# BSF.net
KiCad netlist of a schematic drawn in EAGLE
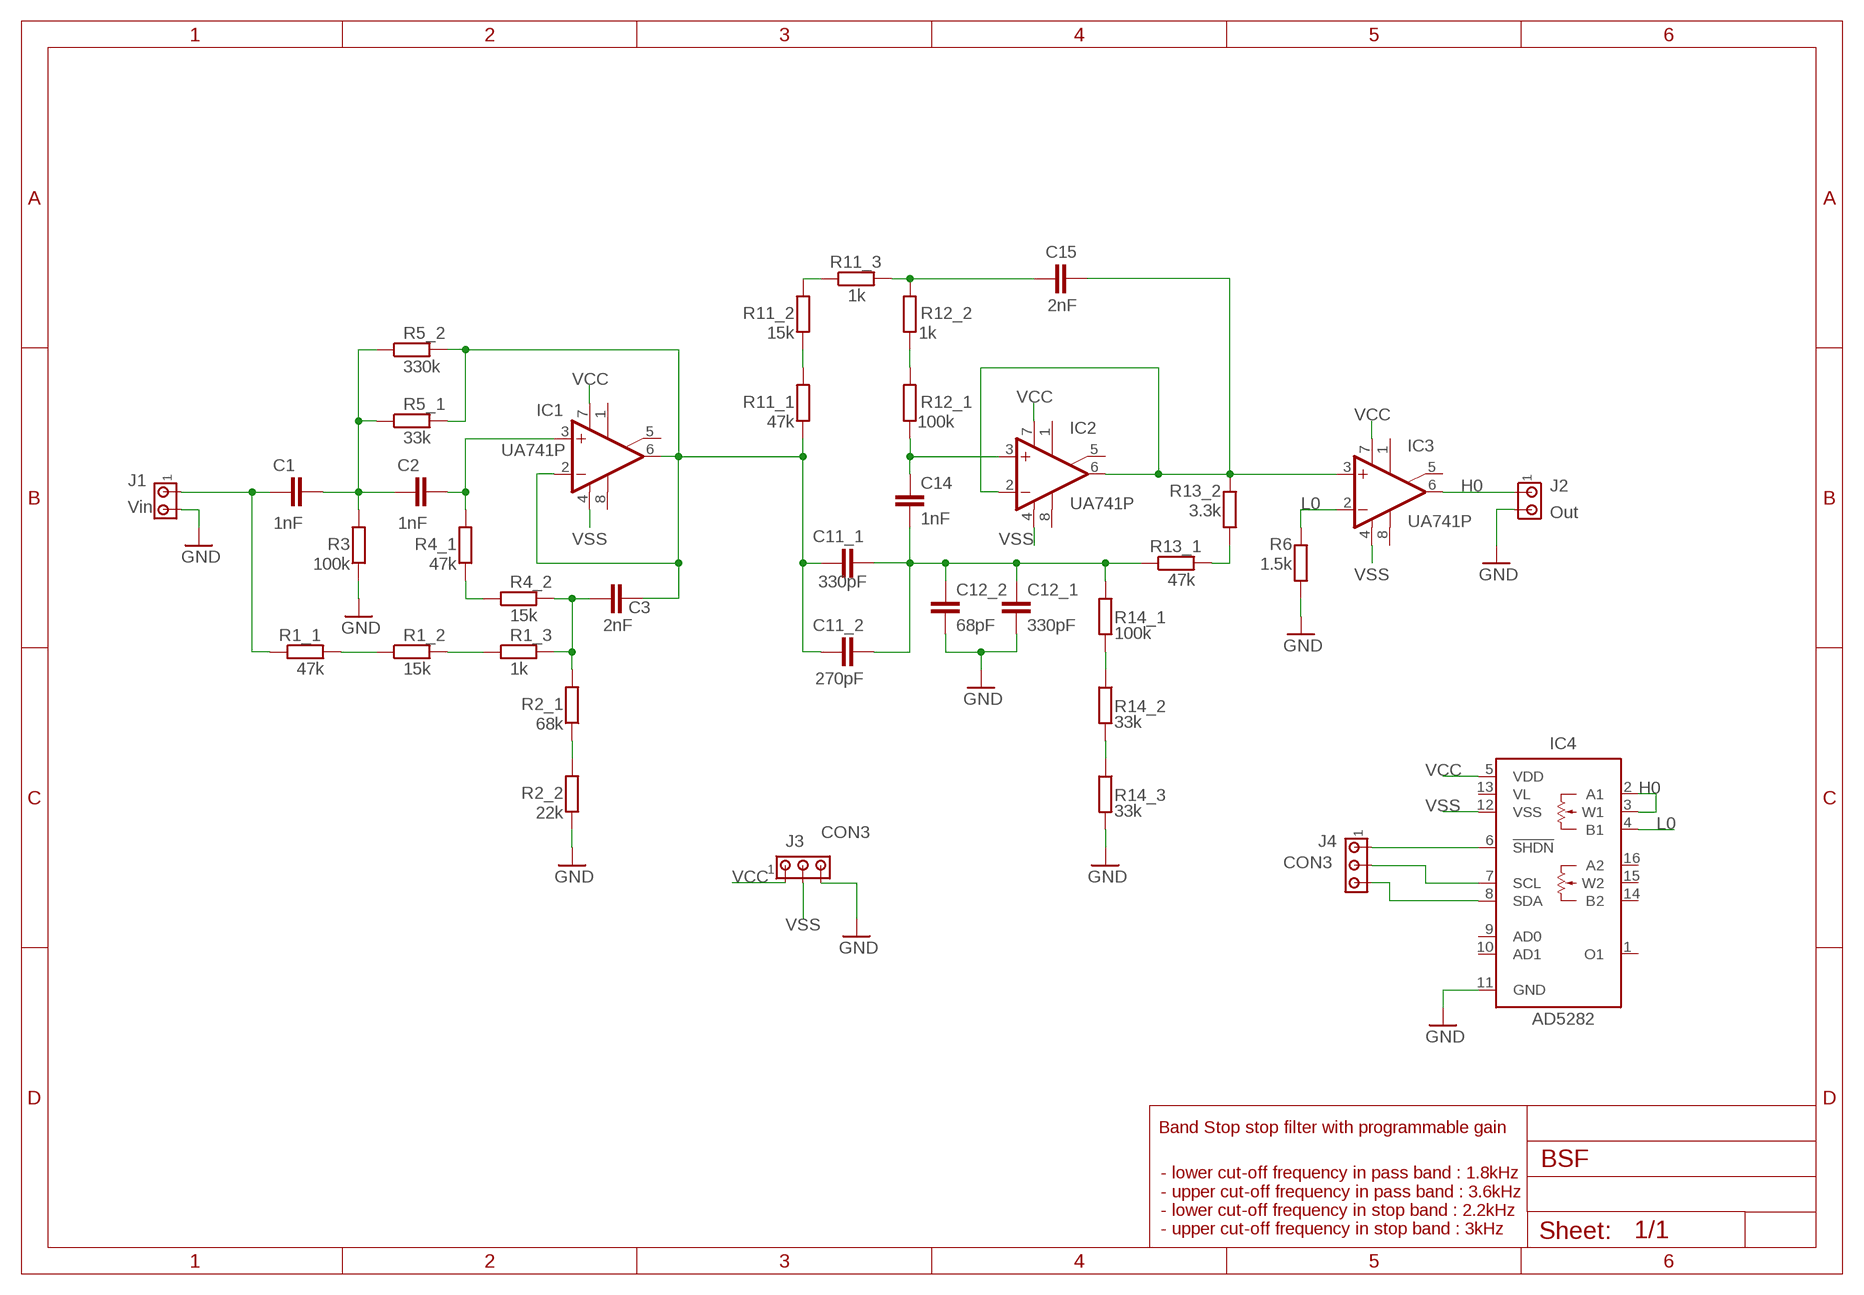
[diagram p0: schematic, sheet 1]

(export (version "E")
  (design (tool "Eeschema 10.0.6"))
  (components
    (comp (ref "C1")
      (value "1nF")
      (footprint "eagle-import:C0805")
      (libsource (lib "eagle-import") (part "C-EUC0805"))
    )
    (comp (ref "C2")
      (value "1nF")
      (footprint "eagle-import:C0805")
      (libsource (lib "eagle-import") (part "C-EUC0805"))
    )
    (comp (ref "C3")
      (value "2nF")
      (footprint "eagle-import:C0805")
      (libsource (lib "eagle-import") (part "C-EUC0805"))
    )
    (comp (ref "C11_1")
      (value "330pF")
      (footprint "eagle-import:C0805")
      (libsource (lib "eagle-import") (part "C-EUC0805"))
    )
    (comp (ref "C11_2")
      (value "270pF")
      (footprint "eagle-import:C0805")
      (libsource (lib "eagle-import") (part "C-EUC0805"))
    )
    (comp (ref "C12_1")
      (value "330pF")
      (footprint "eagle-import:C0805")
      (libsource (lib "eagle-import") (part "C-EUC0805"))
    )
    (comp (ref "C12_2")
      (value "68pF")
      (footprint "eagle-import:C0805")
      (libsource (lib "eagle-import") (part "C-EUC0805"))
    )
    (comp (ref "C14")
      (value "1nF")
      (footprint "eagle-import:C0805")
      (libsource (lib "eagle-import") (part "C-EUC0805"))
    )
    (comp (ref "C15")
      (value "2nF")
      (footprint "eagle-import:C0805")
      (libsource (lib "eagle-import") (part "C-EUC0805"))
    )
    (comp (ref "IC1")
      (value "UA741P")
      (footprint "eagle-import:DIL08")
      (libsource (lib "eagle-import") (part "741PUA"))
    )
    (comp (ref "IC2")
      (value "UA741P")
      (footprint "eagle-import:DIL08")
      (libsource (lib "eagle-import") (part "741PUA"))
    )
    (comp (ref "IC3")
      (value "UA741P")
      (footprint "eagle-import:DIL08")
      (libsource (lib "eagle-import") (part "741PUA"))
    )
    (comp (ref "IC4")
      (value "AD5282")
      (footprint "eagle-import:TSSOP16")
      (fields (field (name "MF") "ALTERA CORPORATION") (field (name "MPN") "AD5282BRUZ50"))
      (libsource (lib "eagle-import") (part "AD5282"))
    )
    (comp (ref "J1")
      (value "Vin")
      (footprint "eagle-import:1X2MTA")
      (libsource (lib "eagle-import") (part "MTA02-156"))
    )
    (comp (ref "J2")
      (value "Out")
      (footprint "eagle-import:1X2MTA")
      (libsource (lib "eagle-import") (part "MTA02-156"))
    )
    (comp (ref "J3")
      (value "CON3")
      (footprint "eagle-import:1X3MTA")
      (libsource (lib "eagle-import") (part "MTA03-156"))
    )
    (comp (ref "J4")
      (value "CON3")
      (footprint "eagle-import:1X3MTA")
      (libsource (lib "eagle-import") (part "MTA03-156"))
    )
    (comp (ref "R1_1")
      (value "47k")
      (footprint "eagle-import:R0805")
      (libsource (lib "eagle-import") (part "R-EU_R0805"))
    )
    (comp (ref "R1_2")
      (value "15k")
      (footprint "eagle-import:R0805")
      (libsource (lib "eagle-import") (part "R-EU_R0805"))
    )
    (comp (ref "R1_3")
      (value "1k")
      (footprint "eagle-import:R0805")
      (libsource (lib "eagle-import") (part "R-EU_R0805"))
    )
    (comp (ref "R2_1")
      (value "68k")
      (footprint "eagle-import:R0805")
      (libsource (lib "eagle-import") (part "R-EU_R0805"))
    )
    (comp (ref "R2_2")
      (value "22k")
      (footprint "eagle-import:R0805")
      (libsource (lib "eagle-import") (part "R-EU_R0805"))
    )
    (comp (ref "R3")
      (value "100k")
      (footprint "eagle-import:R0805")
      (libsource (lib "eagle-import") (part "R-EU_R0805"))
    )
    (comp (ref "R4_1")
      (value "47k")
      (footprint "eagle-import:R0805")
      (libsource (lib "eagle-import") (part "R-EU_R0805"))
    )
    (comp (ref "R4_2")
      (value "15k")
      (footprint "eagle-import:R0805")
      (libsource (lib "eagle-import") (part "R-EU_R0805"))
    )
    (comp (ref "R5_1")
      (value "33k")
      (footprint "eagle-import:R0805")
      (libsource (lib "eagle-import") (part "R-EU_R0805"))
    )
    (comp (ref "R5_2")
      (value "330k")
      (footprint "eagle-import:R0805")
      (libsource (lib "eagle-import") (part "R-EU_R0805"))
    )
    (comp (ref "R6")
      (value "1.5k")
      (footprint "eagle-import:R0805")
      (libsource (lib "eagle-import") (part "R-EU_R0805"))
    )
    (comp (ref "R11_1")
      (value "47k")
      (footprint "eagle-import:R0805")
      (libsource (lib "eagle-import") (part "R-EU_R0805"))
    )
    (comp (ref "R11_2")
      (value "15k")
      (footprint "eagle-import:R0805")
      (libsource (lib "eagle-import") (part "R-EU_R0805"))
    )
    (comp (ref "R11_3")
      (value "1k")
      (footprint "eagle-import:R0805")
      (libsource (lib "eagle-import") (part "R-EU_R0805"))
    )
    (comp (ref "R12_1")
      (value "100k")
      (footprint "eagle-import:R0805")
      (libsource (lib "eagle-import") (part "R-EU_R0805"))
    )
    (comp (ref "R12_2")
      (value "1k")
      (footprint "eagle-import:R0805")
      (libsource (lib "eagle-import") (part "R-EU_R0805"))
    )
    (comp (ref "R13_1")
      (value "47k")
      (footprint "eagle-import:R0805")
      (libsource (lib "eagle-import") (part "R-EU_R0805"))
    )
    (comp (ref "R13_2")
      (value "3.3k")
      (footprint "eagle-import:R0805")
      (libsource (lib "eagle-import") (part "R-EU_R0805"))
    )
    (comp (ref "R14_1")
      (value "100k")
      (footprint "eagle-import:R0805")
      (libsource (lib "eagle-import") (part "R-EU_R0805"))
    )
    (comp (ref "R14_2")
      (value "33k")
      (footprint "eagle-import:R0805")
      (libsource (lib "eagle-import") (part "R-EU_R0805"))
    )
    (comp (ref "R14_3")
      (value "33k")
      (footprint "eagle-import:R0805")
      (libsource (lib "eagle-import") (part "R-EU_R0805"))
    )
  )
  (nets
    (net (code "1") (name "/H0") (class "Default")
      (node (ref "IC3") (pin "6") (pinfunction "OUT_6") (pintype "output"))
      (node (ref "IC4") (pin "2") (pinfunction "A1_2") (pintype "passive"))
      (node (ref "IC4") (pin "3") (pinfunction "W1_3") (pintype "passive"))
      (node (ref "J2") (pin "1") (pinfunction "1_1") (pintype "passive"))
    )
    (net (code "2") (name "/L0") (class "Default")
      (node (ref "IC3") (pin "2") (pinfunction "-IN_2") (pintype "input"))
      (node (ref "IC4") (pin "4") (pinfunction "B1_4") (pintype "passive"))
      (node (ref "R6") (pin "2") (pinfunction "2_2") (pintype "passive"))
    )
    (net (code "3") (name "/VCC") (class "Default")
      (node (ref "IC1") (pin "7") (pinfunction "V+_7") (pintype "power_in"))
      (node (ref "IC2") (pin "7") (pinfunction "V+_7") (pintype "power_in"))
      (node (ref "IC3") (pin "7") (pinfunction "V+_7") (pintype "power_in"))
      (node (ref "IC4") (pin "5") (pinfunction "VDD_5") (pintype "power_in"))
      (node (ref "J3") (pin "1") (pinfunction "1_1") (pintype "passive"))
    )
    (net (code "4") (name "/VL") (class "Default")
      (node (ref "IC4") (pin "13") (pinfunction "VL_13") (pintype "power_in"))
    )
    (net (code "5") (name "/VSS") (class "Default")
      (node (ref "IC1") (pin "4") (pinfunction "V-_4") (pintype "power_in"))
      (node (ref "IC2") (pin "4") (pinfunction "V-_4") (pintype "power_in"))
      (node (ref "IC3") (pin "4") (pinfunction "V-_4") (pintype "power_in"))
      (node (ref "IC4") (pin "12") (pinfunction "VSS_12") (pintype "power_in"))
      (node (ref "J3") (pin "2") (pinfunction "2_2") (pintype "passive"))
    )
    (net (code "6") (name "GND") (class "Default")
      (node (ref "C12_1") (pin "2") (pinfunction "2_2") (pintype "passive"))
      (node (ref "C12_2") (pin "2") (pinfunction "2_2") (pintype "passive"))
      (node (ref "IC4") (pin "11") (pinfunction "GND_11") (pintype "power_in"))
      (node (ref "J1") (pin "2") (pinfunction "2_2") (pintype "passive"))
      (node (ref "J2") (pin "2") (pinfunction "2_2") (pintype "passive"))
      (node (ref "J3") (pin "3") (pinfunction "3_3") (pintype "passive"))
      (node (ref "R14_3") (pin "2") (pinfunction "2_2") (pintype "passive"))
      (node (ref "R2_2") (pin "1") (pinfunction "1_1") (pintype "passive"))
      (node (ref "R3") (pin "1") (pinfunction "1_1") (pintype "passive"))
      (node (ref "R6") (pin "1") (pinfunction "1_1") (pintype "passive"))
    )
    (net (code "7") (name "Net-(C1-Pad1)") (class "Default")
      (node (ref "C1") (pin "1") (pinfunction "1_1") (pintype "passive"))
      (node (ref "J1") (pin "1") (pinfunction "1_1") (pintype "passive"))
      (node (ref "R1_1") (pin "1") (pinfunction "1_1") (pintype "passive"))
    )
    (net (code "8") (name "Net-(C1-Pad2)") (class "Default")
      (node (ref "C1") (pin "2") (pinfunction "2_2") (pintype "passive"))
      (node (ref "C2") (pin "1") (pinfunction "1_1") (pintype "passive"))
      (node (ref "R3") (pin "2") (pinfunction "2_2") (pintype "passive"))
      (node (ref "R5_1") (pin "1") (pinfunction "1_1") (pintype "passive"))
      (node (ref "R5_2") (pin "1") (pinfunction "1_1") (pintype "passive"))
    )
    (net (code "9") (name "Net-(C3-Pad1)") (class "Default")
      (node (ref "C3") (pin "1") (pinfunction "1_1") (pintype "passive"))
      (node (ref "R1_3") (pin "2") (pinfunction "2_2") (pintype "passive"))
      (node (ref "R2_1") (pin "2") (pinfunction "2_2") (pintype "passive"))
      (node (ref "R4_2") (pin "2") (pinfunction "2_2") (pintype "passive"))
    )
    (net (code "10") (name "Net-(C11_1-Pad2)") (class "Default")
      (node (ref "C11_1") (pin "2") (pinfunction "2_2") (pintype "passive"))
      (node (ref "C11_2") (pin "2") (pinfunction "2_2") (pintype "passive"))
      (node (ref "C12_1") (pin "1") (pinfunction "1_1") (pintype "passive"))
      (node (ref "C12_2") (pin "1") (pinfunction "1_1") (pintype "passive"))
      (node (ref "C14") (pin "2") (pinfunction "2_2") (pintype "passive"))
      (node (ref "R13_1") (pin "1") (pinfunction "1_1") (pintype "passive"))
      (node (ref "R14_1") (pin "1") (pinfunction "1_1") (pintype "passive"))
    )
    (net (code "11") (name "Net-(C15-Pad1)") (class "Default")
      (node (ref "C15") (pin "1") (pinfunction "1_1") (pintype "passive"))
      (node (ref "R11_3") (pin "2") (pinfunction "2_2") (pintype "passive"))
      (node (ref "R12_2") (pin "2") (pinfunction "2_2") (pintype "passive"))
    )
    (net (code "12") (name "Net-(IC1-+IN)") (class "Default")
      (node (ref "C2") (pin "2") (pinfunction "2_2") (pintype "passive"))
      (node (ref "IC1") (pin "3") (pinfunction "+IN_3") (pintype "input"))
      (node (ref "R4_1") (pin "2") (pinfunction "2_2") (pintype "passive"))
    )
    (net (code "13") (name "Net-(IC1--IN)") (class "Default")
      (node (ref "C11_1") (pin "1") (pinfunction "1_1") (pintype "passive"))
      (node (ref "C11_2") (pin "1") (pinfunction "1_1") (pintype "passive"))
      (node (ref "C3") (pin "2") (pinfunction "2_2") (pintype "passive"))
      (node (ref "IC1") (pin "2") (pinfunction "-IN_2") (pintype "input"))
      (node (ref "IC1") (pin "6") (pinfunction "OUT_6") (pintype "output"))
      (node (ref "R11_1") (pin "1") (pinfunction "1_1") (pintype "passive"))
      (node (ref "R5_1") (pin "2") (pinfunction "2_2") (pintype "passive"))
      (node (ref "R5_2") (pin "2") (pinfunction "2_2") (pintype "passive"))
    )
    (net (code "14") (name "Net-(IC2-+IN)") (class "Default")
      (node (ref "C14") (pin "1") (pinfunction "1_1") (pintype "passive"))
      (node (ref "IC2") (pin "3") (pinfunction "+IN_3") (pintype "input"))
      (node (ref "R12_1") (pin "1") (pinfunction "1_1") (pintype "passive"))
    )
    (net (code "15") (name "Net-(IC2--IN)") (class "Default")
      (node (ref "C15") (pin "2") (pinfunction "2_2") (pintype "passive"))
      (node (ref "IC2") (pin "2") (pinfunction "-IN_2") (pintype "input"))
      (node (ref "IC2") (pin "6") (pinfunction "OUT_6") (pintype "output"))
      (node (ref "IC3") (pin "3") (pinfunction "+IN_3") (pintype "input"))
      (node (ref "R13_2") (pin "2") (pinfunction "2_2") (pintype "passive"))
    )
    (net (code "16") (name "Net-(IC4-SCL)") (class "Default")
      (node (ref "IC4") (pin "7") (pinfunction "SCL_7") (pintype "input"))
      (node (ref "J4") (pin "2") (pinfunction "2_2") (pintype "passive"))
    )
    (net (code "17") (name "Net-(IC4-SDA)") (class "Default")
      (node (ref "IC4") (pin "8") (pinfunction "SDA_8") (pintype "bidirectional"))
      (node (ref "J4") (pin "3") (pinfunction "3_3") (pintype "passive"))
    )
    (net (code "18") (name "Net-(IC4-~{SHDN})") (class "Default")
      (node (ref "IC4") (pin "6") (pinfunction "~{SHDN}_6") (pintype "input"))
      (node (ref "J4") (pin "1") (pinfunction "1_1") (pintype "passive"))
    )
    (net (code "19") (name "Net-(R1_1-Pad2)") (class "Default")
      (node (ref "R1_1") (pin "2") (pinfunction "2_2") (pintype "passive"))
      (node (ref "R1_2") (pin "1") (pinfunction "1_1") (pintype "passive"))
    )
    (net (code "20") (name "Net-(R1_2-Pad2)") (class "Default")
      (node (ref "R1_2") (pin "2") (pinfunction "2_2") (pintype "passive"))
      (node (ref "R1_3") (pin "1") (pinfunction "1_1") (pintype "passive"))
    )
    (net (code "21") (name "Net-(R2_1-Pad1)") (class "Default")
      (node (ref "R2_1") (pin "1") (pinfunction "1_1") (pintype "passive"))
      (node (ref "R2_2") (pin "2") (pinfunction "2_2") (pintype "passive"))
    )
    (net (code "22") (name "Net-(R4_1-Pad1)") (class "Default")
      (node (ref "R4_1") (pin "1") (pinfunction "1_1") (pintype "passive"))
      (node (ref "R4_2") (pin "1") (pinfunction "1_1") (pintype "passive"))
    )
    (net (code "23") (name "Net-(R11_1-Pad2)") (class "Default")
      (node (ref "R11_1") (pin "2") (pinfunction "2_2") (pintype "passive"))
      (node (ref "R11_2") (pin "1") (pinfunction "1_1") (pintype "passive"))
    )
    (net (code "24") (name "Net-(R11_2-Pad2)") (class "Default")
      (node (ref "R11_2") (pin "2") (pinfunction "2_2") (pintype "passive"))
      (node (ref "R11_3") (pin "1") (pinfunction "1_1") (pintype "passive"))
    )
    (net (code "25") (name "Net-(R12_1-Pad2)") (class "Default")
      (node (ref "R12_1") (pin "2") (pinfunction "2_2") (pintype "passive"))
      (node (ref "R12_2") (pin "1") (pinfunction "1_1") (pintype "passive"))
    )
    (net (code "26") (name "Net-(R13_1-Pad2)") (class "Default")
      (node (ref "R13_1") (pin "2") (pinfunction "2_2") (pintype "passive"))
      (node (ref "R13_2") (pin "1") (pinfunction "1_1") (pintype "passive"))
    )
    (net (code "27") (name "Net-(R14_1-Pad2)") (class "Default")
      (node (ref "R14_1") (pin "2") (pinfunction "2_2") (pintype "passive"))
      (node (ref "R14_2") (pin "1") (pinfunction "1_1") (pintype "passive"))
    )
    (net (code "28") (name "Net-(R14_2-Pad2)") (class "Default")
      (node (ref "R14_2") (pin "2") (pinfunction "2_2") (pintype "passive"))
      (node (ref "R14_3") (pin "1") (pinfunction "1_1") (pintype "passive"))
    )
    (net (code "29") (name "unconnected-(IC1-ON1-Pad1)") (class "Default")
      (node (ref "IC1") (pin "1") (pinfunction "ON1_1") (pintype "passive"))
    )
    (net (code "30") (name "unconnected-(IC1-ON2-Pad5)") (class "Default")
      (node (ref "IC1") (pin "5") (pinfunction "ON2_5") (pintype "passive"))
    )
    (net (code "31") (name "unconnected-(IC1-OPT-Pad8)") (class "Default")
      (node (ref "IC1") (pin "8") (pinfunction "OPT_8") (pintype "passive"))
    )
    (net (code "32") (name "unconnected-(IC2-ON1-Pad1)") (class "Default")
      (node (ref "IC2") (pin "1") (pinfunction "ON1_1") (pintype "passive"))
    )
    (net (code "33") (name "unconnected-(IC2-ON2-Pad5)") (class "Default")
      (node (ref "IC2") (pin "5") (pinfunction "ON2_5") (pintype "passive"))
    )
    (net (code "34") (name "unconnected-(IC2-OPT-Pad8)") (class "Default")
      (node (ref "IC2") (pin "8") (pinfunction "OPT_8") (pintype "passive"))
    )
    (net (code "35") (name "unconnected-(IC3-ON1-Pad1)") (class "Default")
      (node (ref "IC3") (pin "1") (pinfunction "ON1_1") (pintype "passive"))
    )
    (net (code "36") (name "unconnected-(IC3-ON2-Pad5)") (class "Default")
      (node (ref "IC3") (pin "5") (pinfunction "ON2_5") (pintype "passive"))
    )
    (net (code "37") (name "unconnected-(IC3-OPT-Pad8)") (class "Default")
      (node (ref "IC3") (pin "8") (pinfunction "OPT_8") (pintype "passive"))
    )
    (net (code "38") (name "unconnected-(IC4-A2-Pad16)") (class "Default")
      (node (ref "IC4") (pin "16") (pinfunction "A2_16") (pintype "passive"))
    )
    (net (code "39") (name "unconnected-(IC4-AD0-Pad9)") (class "Default")
      (node (ref "IC4") (pin "9") (pinfunction "AD0_9") (pintype "input"))
    )
    (net (code "40") (name "unconnected-(IC4-AD1-Pad10)") (class "Default")
      (node (ref "IC4") (pin "10") (pinfunction "AD1_10") (pintype "input"))
    )
    (net (code "41") (name "unconnected-(IC4-B2-Pad14)") (class "Default")
      (node (ref "IC4") (pin "14") (pinfunction "B2_14") (pintype "passive"))
    )
    (net (code "42") (name "unconnected-(IC4-O1-Pad1)") (class "Default")
      (node (ref "IC4") (pin "1") (pinfunction "O1_1") (pintype "output"))
    )
    (net (code "43") (name "unconnected-(IC4-W2-Pad15)") (class "Default")
      (node (ref "IC4") (pin "15") (pinfunction "W2_15") (pintype "passive"))
    )
  )
)
